# BM1370_REFCLK.net
KiCad netlist of a schematic drawn in Altium Designer
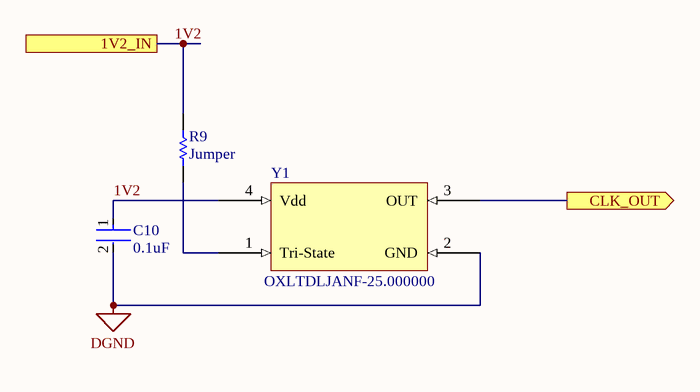
[diagram p0: BM1370_REFCLK.SchDoc]

(export (version "E")
  (design (tool "Eeschema 10.0.6"))
  (components
    (comp (ref "C10")
      (value "0.1uF")
      (footprint "FP-CC0402-IPC_C")
      (description "Multilayer Ceramic Capacitor, 0.1 uF, 25 V, ± 10%, X7R, 0402 [1005 Metric]")
      (fields (field (name "Comment") "CC0402KRX7R7BB104"))
      (libsource (lib "Digital Shovel") (part "11868f565c42a9108669ba33697ecf6"))
    )
    (comp (ref "R9")
      (value "Jumper")
      (footprint "FP-RK73Z1E-IPC_B")
      (description "Metal Glaze/thick Film, 0ohm, Surface Mount, 0402")
      (fields (field (name "Comment") "RK73Z1ETTP"))
      (libsource (lib "Digital Shovel") (part "1029c3af85768c4190bb7ad29bc67b5"))
    )
    (comp (ref "Y1")
      (value "OXLTDLJANF-25.000000")
      (footprint "OXLTDLJANF-25.000000-Footprint-1")
      (description "Xtal Osc Xo 25MHZ 1.2V Cmos SMD")
      (libsource (lib "Digital Shovel") (part "OXLTDLJANF-25.000000"))
    )
  )
  (nets
    (net (code "1") (name "/1V2") (class "Default")
      (node (ref "C10") (pin "1") (pinfunction "1_1") (pintype "passive"))
      (node (ref "R9") (pin "2") (pinfunction "2_2") (pintype "passive"))
      (node (ref "Y1") (pin "4") (pinfunction "Vdd_4") (pintype "input"))
    )
    (net (code "2") (name "/CLK_OUT") (class "Default")
      (node (ref "Y1") (pin "3") (pinfunction "OUT_3") (pintype "input"))
    )
    (net (code "3") (name "DGND") (class "Default")
      (node (ref "C10") (pin "2") (pinfunction "2_2") (pintype "passive"))
      (node (ref "Y1") (pin "2") (pinfunction "GND_2") (pintype "input"))
    )
    (net (code "4") (name "Net-(Y1-Tri-State)") (class "Default")
      (node (ref "R9") (pin "1") (pinfunction "1_1") (pintype "passive"))
      (node (ref "Y1") (pin "1") (pinfunction "Tri-State_1") (pintype "input"))
    )
  )
)
